# 4_Connectors.net
KiCad netlist of a schematic drawn in Altium Designer
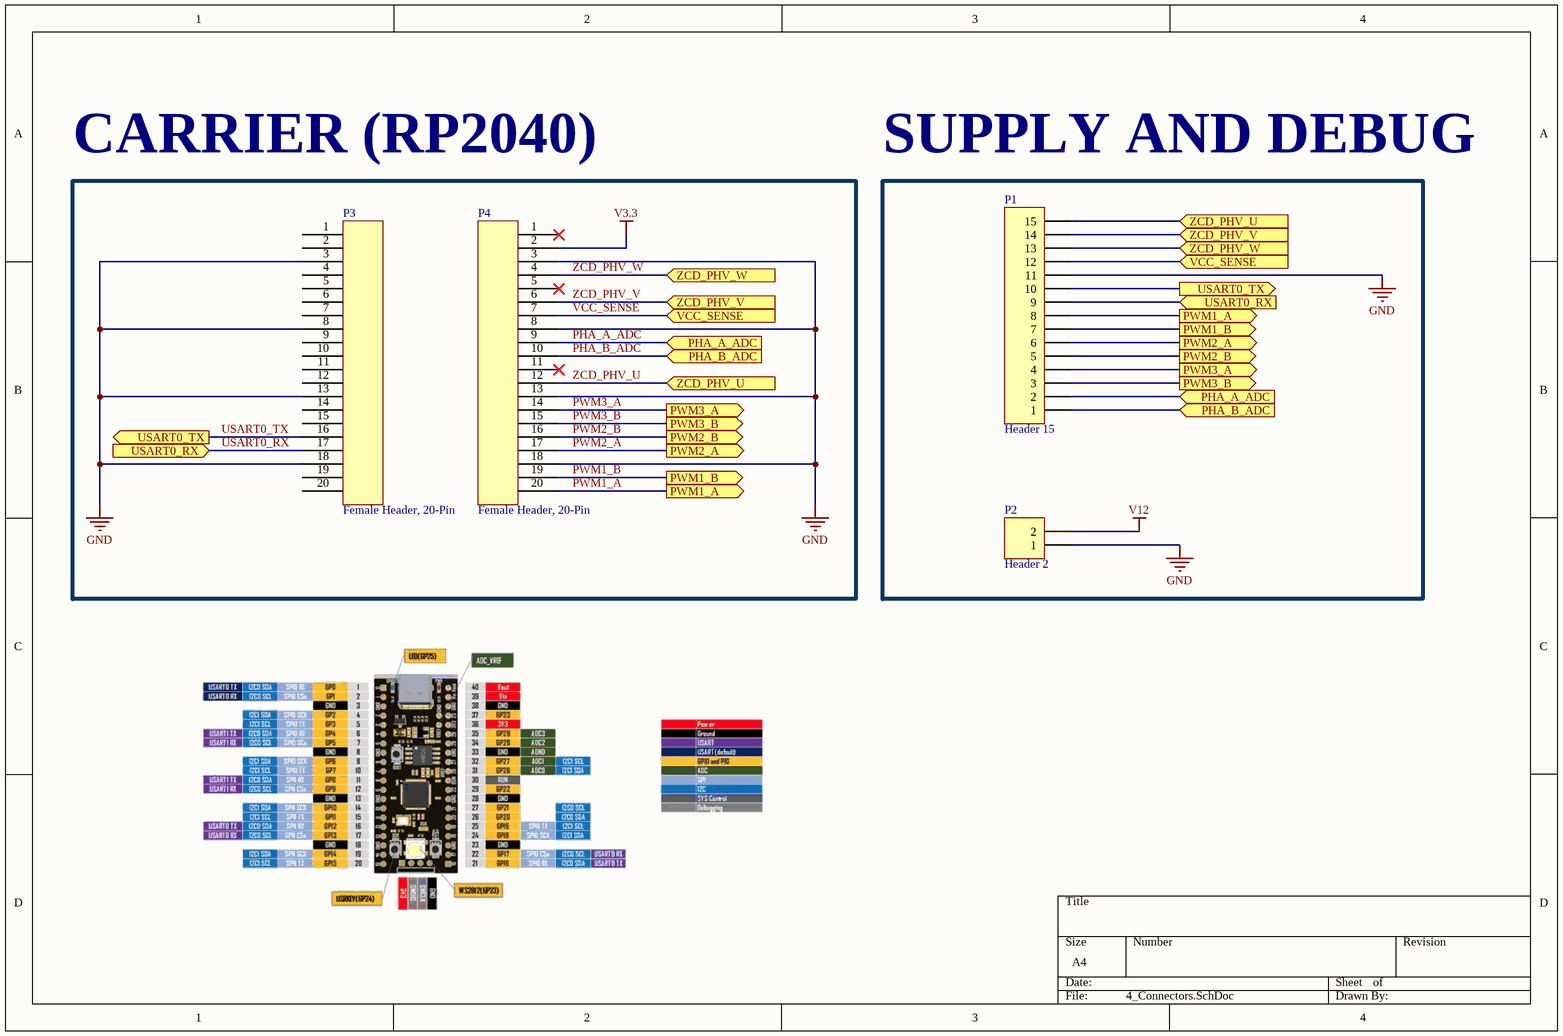
[diagram p0: 4_Connectors.SchDoc]

(export (version "E")
  (design (tool "Eeschema 10.0.6"))
  (components
    (comp (ref "P1")
      (value "Header 15")
      (footprint "Milibreria:HDR1X15")
      (description "Header, 15-Pin")
      (fields (field (name "PUBLISHER") "Altium Limited"))
      (libsource (lib "Miscellaneous Connectors") (part "Header 15"))
    )
    (comp (ref "P2")
      (value "Header 2")
      (footprint "Milibreria:Screw Header 2 (5 mm pitch)")
      (description "Header, 2-Pin")
      (fields (field (name "PUBLISHER") "Altium Limited"))
      (libsource (lib "Miscellaneous Connectors") (part "Header 2"))
    )
    (comp (ref "P3")
      (value "Female Header, 20-Pin")
      (footprint "HEADER 20")
      (libsource (lib "") (part "Header 20_1"))
    )
    (comp (ref "P4")
      (value "Female Header, 20-Pin")
      (footprint "HEADER 20")
      (libsource (lib "BLDC_BridgeBoard_V1_2") (part "Header 20"))
    )
  )
  (nets
    (net (code "1") (name "/PHA_A_ADC") (class "Default")
      (node (ref "P1") (pin "2") (pinfunction "2_2") (pintype "passive"))
      (node (ref "P4") (pin "9") (pintype "passive"))
    )
    (net (code "2") (name "/PHA_B_ADC") (class "Default")
      (node (ref "P1") (pin "1") (pinfunction "1_1") (pintype "passive"))
      (node (ref "P4") (pin "10") (pintype "passive"))
    )
    (net (code "3") (name "/PWM1_A") (class "Default")
      (node (ref "P1") (pin "8") (pinfunction "8_8") (pintype "passive"))
      (node (ref "P4") (pin "20") (pintype "passive"))
    )
    (net (code "4") (name "/PWM1_B") (class "Default")
      (node (ref "P1") (pin "7") (pinfunction "7_7") (pintype "passive"))
      (node (ref "P4") (pin "19") (pintype "passive"))
    )
    (net (code "5") (name "/PWM2_A") (class "Default")
      (node (ref "P1") (pin "6") (pinfunction "6_6") (pintype "passive"))
      (node (ref "P4") (pin "17") (pintype "passive"))
    )
    (net (code "6") (name "/PWM2_B") (class "Default")
      (node (ref "P1") (pin "5") (pinfunction "5_5") (pintype "passive"))
      (node (ref "P4") (pin "16") (pintype "passive"))
    )
    (net (code "7") (name "/PWM3_A") (class "Default")
      (node (ref "P1") (pin "4") (pinfunction "4_4") (pintype "passive"))
      (node (ref "P4") (pin "14") (pintype "passive"))
    )
    (net (code "8") (name "/PWM3_B") (class "Default")
      (node (ref "P1") (pin "3") (pinfunction "3_3") (pintype "passive"))
      (node (ref "P4") (pin "15") (pintype "passive"))
    )
    (net (code "9") (name "/USART0_RX") (class "Default")
      (node (ref "P1") (pin "9") (pinfunction "9_9") (pintype "passive"))
      (node (ref "P3") (pin "17") (pintype "passive"))
    )
    (net (code "10") (name "/USART0_TX") (class "Default")
      (node (ref "P1") (pin "10") (pinfunction "10_10") (pintype "passive"))
      (node (ref "P3") (pin "16") (pintype "passive"))
    )
    (net (code "11") (name "/VCC_SENSE") (class "Default")
      (node (ref "P1") (pin "12") (pinfunction "12_12") (pintype "passive"))
      (node (ref "P4") (pin "7") (pintype "passive"))
    )
    (net (code "12") (name "/ZCD_PHV_U") (class "Default")
      (node (ref "P1") (pin "15") (pinfunction "15_15") (pintype "passive"))
      (node (ref "P4") (pin "12") (pintype "passive"))
    )
    (net (code "13") (name "/ZCD_PHV_V") (class "Default")
      (node (ref "P1") (pin "14") (pinfunction "14_14") (pintype "passive"))
      (node (ref "P4") (pin "6") (pintype "passive"))
    )
    (net (code "14") (name "/ZCD_PHV_W") (class "Default")
      (node (ref "P1") (pin "13") (pinfunction "13_13") (pintype "passive"))
      (node (ref "P4") (pin "4") (pintype "passive"))
    )
    (net (code "15") (name "GND") (class "Default")
      (node (ref "P1") (pin "11") (pinfunction "11_11") (pintype "passive"))
      (node (ref "P2") (pin "1") (pinfunction "1_1") (pintype "passive"))
      (node (ref "P3") (pin "13") (pintype "passive"))
      (node (ref "P3") (pin "18") (pintype "passive"))
      (node (ref "P3") (pin "3") (pintype "passive"))
      (node (ref "P3") (pin "8") (pintype "passive"))
      (node (ref "P4") (pin "13") (pintype "passive"))
      (node (ref "P4") (pin "18") (pintype "passive"))
      (node (ref "P4") (pin "3") (pintype "passive"))
      (node (ref "P4") (pin "8") (pintype "passive"))
    )
    (net (code "16") (name "V3.3") (class "Default") (node (ref "P4") (pin "2") (pintype "passive")))
    (net (code "17") (name "V12") (class "Default")
      (node (ref "P2") (pin "2") (pinfunction "2_2") (pintype "passive"))
    )
    (net (code "18") (name "unconnected-(P3-Pad1)") (class "Default")
      (node (ref "P3") (pin "1") (pintype "passive"))
    )
    (net (code "19") (name "unconnected-(P3-Pad2)") (class "Default")
      (node (ref "P3") (pin "2") (pintype "passive"))
    )
    (net (code "20") (name "unconnected-(P3-Pad4)") (class "Default")
      (node (ref "P3") (pin "4") (pintype "passive"))
    )
    (net (code "21") (name "unconnected-(P3-Pad5)") (class "Default")
      (node (ref "P3") (pin "5") (pintype "passive"))
    )
    (net (code "22") (name "unconnected-(P3-Pad6)") (class "Default")
      (node (ref "P3") (pin "6") (pintype "passive"))
    )
    (net (code "23") (name "unconnected-(P3-Pad7)") (class "Default")
      (node (ref "P3") (pin "7") (pintype "passive"))
    )
    (net (code "24") (name "unconnected-(P3-Pad9)") (class "Default")
      (node (ref "P3") (pin "9") (pintype "passive"))
    )
    (net (code "25") (name "unconnected-(P3-Pad10)") (class "Default")
      (node (ref "P3") (pin "10") (pintype "passive"))
    )
    (net (code "26") (name "unconnected-(P3-Pad11)") (class "Default")
      (node (ref "P3") (pin "11") (pintype "passive"))
    )
    (net (code "27") (name "unconnected-(P3-Pad12)") (class "Default")
      (node (ref "P3") (pin "12") (pintype "passive"))
    )
    (net (code "28") (name "unconnected-(P3-Pad14)") (class "Default")
      (node (ref "P3") (pin "14") (pintype "passive"))
    )
    (net (code "29") (name "unconnected-(P3-Pad15)") (class "Default")
      (node (ref "P3") (pin "15") (pintype "passive"))
    )
    (net (code "30") (name "unconnected-(P3-Pad19)") (class "Default")
      (node (ref "P3") (pin "19") (pintype "passive"))
    )
    (net (code "31") (name "unconnected-(P3-Pad20)") (class "Default")
      (node (ref "P3") (pin "20") (pintype "passive"))
    )
    (net (code "32") (name "unconnected-(P4-Pad1)") (class "Default")
      (node (ref "P4") (pin "1") (pintype "passive+no_connect"))
    )
    (net (code "33") (name "unconnected-(P4-Pad5)") (class "Default")
      (node (ref "P4") (pin "5") (pintype "passive+no_connect"))
    )
    (net (code "34") (name "unconnected-(P4-Pad11)") (class "Default")
      (node (ref "P4") (pin "11") (pintype "passive+no_connect"))
    )
  )
)
